# Arduino_Heated_Seats_Controller.net
KiCad netlist of a schematic drawn in EAGLE
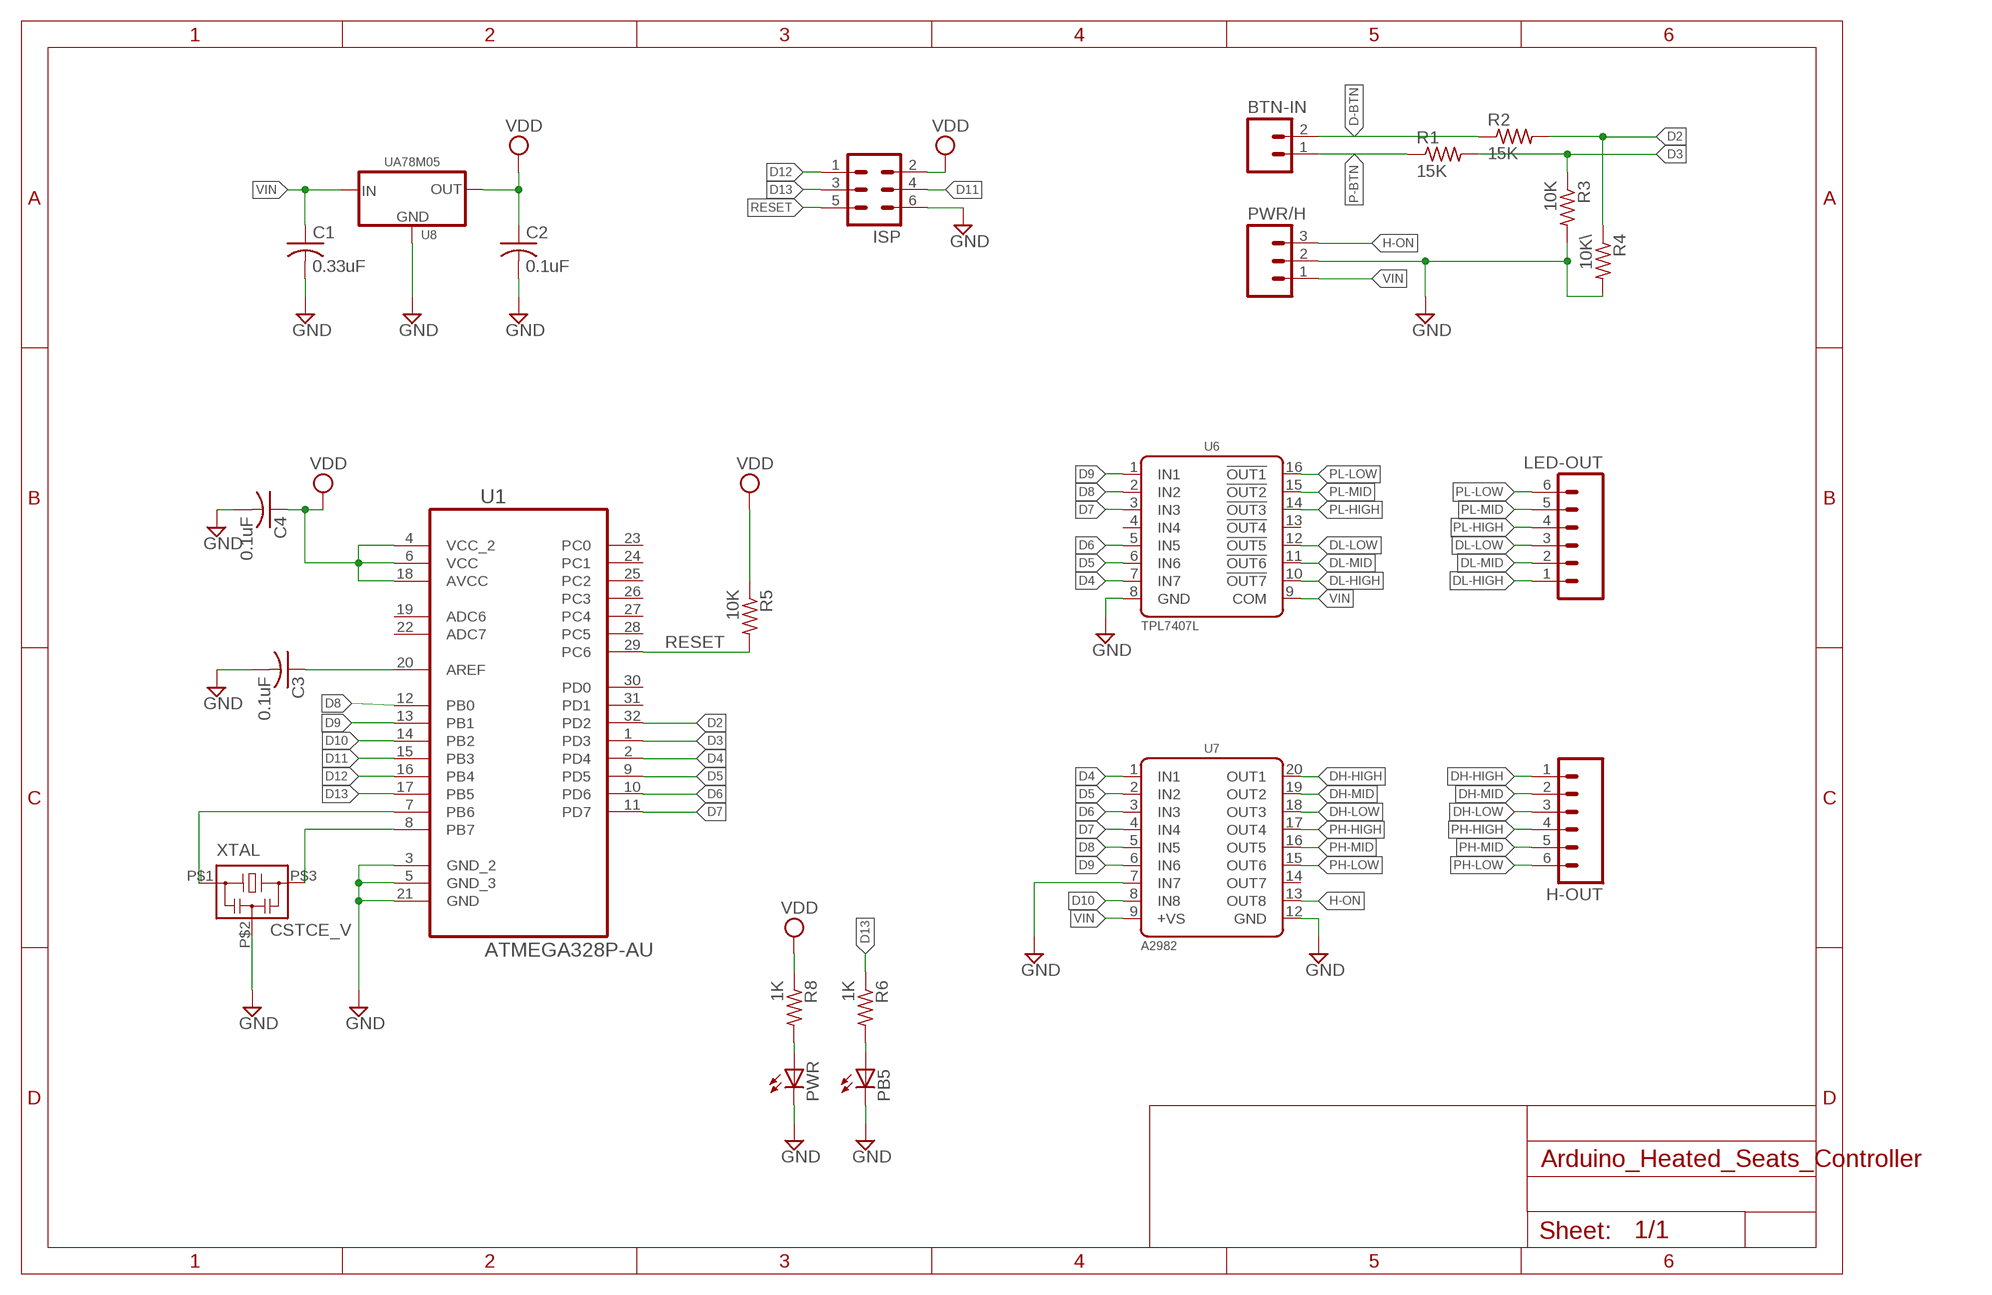
[diagram p0: schematic, sheet 1]

(export (version "E")
  (design (tool "Eeschema 10.0.6"))
  (components
    (comp (ref "BTN-IN")
      (value "M02PTH")
      (footprint "eagle-import:1X02")
      (libsource (lib "eagle-import") (part "M02PTH"))
    )
    (comp (ref "C1")
      (value "0.33uF")
      (footprint "eagle-import:C0603")
      (libsource (lib "eagle-import") (part "C-USC0603"))
    )
    (comp (ref "C2")
      (value "0.1uF")
      (footprint "eagle-import:C0603")
      (libsource (lib "eagle-import") (part "C-USC0603"))
    )
    (comp (ref "C3")
      (value "0.1uF")
      (footprint "eagle-import:C0603")
      (libsource (lib "eagle-import") (part "C-USC0603"))
    )
    (comp (ref "C4")
      (value "0.1uF")
      (footprint "eagle-import:C0603")
      (libsource (lib "eagle-import") (part "C-USC0603"))
    )
    (comp (ref "H-OUT")
      (value "M06SIP")
      (footprint "eagle-import:1X06")
      (libsource (lib "eagle-import") (part "M06SIP"))
    )
    (comp (ref "ISP")
      (value "MA03-2")
      (footprint "eagle-import:MA03-2")
      (libsource (lib "eagle-import") (part "MA03-2"))
    )
    (comp (ref "LED-OUT")
      (value "M06SIP")
      (footprint "eagle-import:1X06")
      (libsource (lib "eagle-import") (part "M06SIP"))
    )
    (comp (ref "PB5")
      (value "LEDCHIP-LED0603")
      (footprint "eagle-import:CHIP-LED0603")
      (libsource (lib "eagle-import") (part "LEDCHIP-LED0603"))
    )
    (comp (ref "PWR")
      (value "LEDCHIP-LED0603")
      (footprint "eagle-import:CHIP-LED0603")
      (libsource (lib "eagle-import") (part "LEDCHIP-LED0603"))
    )
    (comp (ref "PWR/H")
      (value "M03PTH")
      (footprint "eagle-import:1X03")
      (libsource (lib "eagle-import") (part "M03PTH"))
    )
    (comp (ref "R1")
      (value "15K")
      (footprint "eagle-import:R0603")
      (libsource (lib "eagle-import") (part "R-US_R0603"))
    )
    (comp (ref "R2")
      (value "15K")
      (footprint "eagle-import:R0603")
      (libsource (lib "eagle-import") (part "R-US_R0603"))
    )
    (comp (ref "R3")
      (value "10K")
      (footprint "eagle-import:R0603")
      (libsource (lib "eagle-import") (part "R-US_R0603"))
    )
    (comp (ref "R4")
      (value "10K\\")
      (footprint "eagle-import:R0603")
      (libsource (lib "eagle-import") (part "R-US_R0603"))
    )
    (comp (ref "R5")
      (value "10K")
      (footprint "eagle-import:R0603")
      (libsource (lib "eagle-import") (part "R-US_R0603"))
    )
    (comp (ref "R6")
      (value "1K")
      (footprint "eagle-import:R0603")
      (libsource (lib "eagle-import") (part "R-US_R0603"))
    )
    (comp (ref "R8")
      (value "1K")
      (footprint "eagle-import:R0603")
      (libsource (lib "eagle-import") (part "R-US_R0603"))
    )
    (comp (ref "U1")
      (value "ATMEGA328P-AU")
      (footprint "eagle-import:QFP80P900X900X120-32N")
      (libsource (lib "eagle-import") (part "ATMEGA328P-AU"))
    )
    (comp (ref "U6")
      (value "TPL7407L")
      (footprint "eagle-import:SOIC16N")
      (libsource (lib "eagle-import") (part "TPL7407L"))
    )
    (comp (ref "U7")
      (value "A2982")
      (footprint "eagle-import:SOIC20W")
      (libsource (lib "eagle-import") (part "A2982"))
    )
    (comp (ref "U8")
      (value "UA78M05")
      (footprint "eagle-import:SOT223")
      (libsource (lib "eagle-import") (part "UA78M05"))
    )
    (comp (ref "XTAL")
      (value "CSTCE_V")
      (footprint "eagle-import:CSTCE_V")
      (libsource (lib "eagle-import") (part "CSTCE_V"))
    )
  )
  (nets
    (net (code "1") (name "D-BTN") (class "Default")
      (node (ref "BTN-IN") (pin "2") (pinfunction "2_2") (pintype "passive"))
      (node (ref "R2") (pin "1") (pinfunction "1_1") (pintype "passive"))
    )
    (net (code "2") (name "D2") (class "Default")
      (node (ref "R2") (pin "2") (pinfunction "2_2") (pintype "passive"))
      (node (ref "R4") (pin "1") (pinfunction "1_1") (pintype "passive"))
      (node (ref "U1") (pin "32") (pinfunction "PD2_32") (pintype "bidirectional"))
    )
    (net (code "3") (name "D3") (class "Default")
      (node (ref "R1") (pin "2") (pinfunction "2_2") (pintype "passive"))
      (node (ref "R3") (pin "1") (pinfunction "1_1") (pintype "passive"))
      (node (ref "U1") (pin "1") (pinfunction "PD3_1") (pintype "bidirectional"))
    )
    (net (code "4") (name "D4") (class "Default")
      (node (ref "U1") (pin "2") (pinfunction "PD4_2") (pintype "bidirectional"))
      (node (ref "U6") (pin "7") (pinfunction "IN7_7") (pintype "bidirectional"))
      (node (ref "U7") (pin "1") (pinfunction "IN1_1") (pintype "bidirectional"))
    )
    (net (code "5") (name "D5") (class "Default")
      (node (ref "U1") (pin "9") (pinfunction "PD5_9") (pintype "bidirectional"))
      (node (ref "U6") (pin "6") (pinfunction "IN6_6") (pintype "bidirectional"))
      (node (ref "U7") (pin "2") (pinfunction "IN2_2") (pintype "bidirectional"))
    )
    (net (code "6") (name "D6") (class "Default")
      (node (ref "U1") (pin "10") (pinfunction "PD6_10") (pintype "bidirectional"))
      (node (ref "U6") (pin "5") (pinfunction "IN5_5") (pintype "bidirectional"))
      (node (ref "U7") (pin "3") (pinfunction "IN3_3") (pintype "bidirectional"))
    )
    (net (code "7") (name "D7") (class "Default")
      (node (ref "U1") (pin "11") (pinfunction "PD7_11") (pintype "bidirectional"))
      (node (ref "U6") (pin "3") (pinfunction "IN3_3") (pintype "bidirectional"))
      (node (ref "U7") (pin "4") (pinfunction "IN4_4") (pintype "bidirectional"))
    )
    (net (code "8") (name "D8") (class "Default")
      (node (ref "U1") (pin "12") (pinfunction "PB0_12") (pintype "bidirectional"))
      (node (ref "U6") (pin "2") (pinfunction "IN2_2") (pintype "bidirectional"))
      (node (ref "U7") (pin "5") (pinfunction "IN5_5") (pintype "bidirectional"))
    )
    (net (code "9") (name "D9") (class "Default")
      (node (ref "U1") (pin "13") (pinfunction "PB1_13") (pintype "bidirectional"))
      (node (ref "U6") (pin "1") (pinfunction "IN1_1") (pintype "bidirectional"))
      (node (ref "U7") (pin "6") (pinfunction "IN6_6") (pintype "bidirectional"))
    )
    (net (code "10") (name "D10") (class "Default")
      (node (ref "U1") (pin "14") (pinfunction "PB2_14") (pintype "bidirectional"))
      (node (ref "U7") (pin "8") (pinfunction "IN8_8") (pintype "bidirectional"))
    )
    (net (code "11") (name "D11") (class "Default")
      (node (ref "ISP") (pin "4") (pinfunction "4_4") (pintype "passive"))
      (node (ref "U1") (pin "15") (pinfunction "PB3_15") (pintype "bidirectional"))
    )
    (net (code "12") (name "D12") (class "Default")
      (node (ref "ISP") (pin "1") (pinfunction "1_1") (pintype "passive"))
      (node (ref "U1") (pin "16") (pinfunction "PB4_16") (pintype "bidirectional"))
    )
    (net (code "13") (name "D13") (class "Default")
      (node (ref "ISP") (pin "3") (pinfunction "3_3") (pintype "passive"))
      (node (ref "R6") (pin "1") (pinfunction "1_1") (pintype "passive"))
      (node (ref "U1") (pin "17") (pinfunction "PB5_17") (pintype "bidirectional"))
    )
    (net (code "14") (name "DH-HIGH") (class "Default")
      (node (ref "H-OUT") (pin "1") (pinfunction "1_1") (pintype "passive"))
      (node (ref "U7") (pin "20") (pinfunction "OUT1_20") (pintype "bidirectional"))
    )
    (net (code "15") (name "DH-LOW") (class "Default")
      (node (ref "H-OUT") (pin "3") (pinfunction "3_3") (pintype "passive"))
      (node (ref "U7") (pin "18") (pinfunction "OUT3_18") (pintype "bidirectional"))
    )
    (net (code "16") (name "DH-MID") (class "Default")
      (node (ref "H-OUT") (pin "2") (pinfunction "2_2") (pintype "passive"))
      (node (ref "U7") (pin "19") (pinfunction "OUT2_19") (pintype "bidirectional"))
    )
    (net (code "17") (name "DL-HIGH") (class "Default")
      (node (ref "LED-OUT") (pin "1") (pinfunction "1_1") (pintype "passive"))
      (node (ref "U6") (pin "10") (pinfunction "~{OUT7}_10") (pintype "bidirectional"))
    )
    (net (code "18") (name "DL-LOW") (class "Default")
      (node (ref "LED-OUT") (pin "3") (pinfunction "3_3") (pintype "passive"))
      (node (ref "U6") (pin "12") (pinfunction "~{OUT5}_12") (pintype "bidirectional"))
    )
    (net (code "19") (name "DL-MID") (class "Default")
      (node (ref "LED-OUT") (pin "2") (pinfunction "2_2") (pintype "passive"))
      (node (ref "U6") (pin "11") (pinfunction "~{OUT6}_11") (pintype "bidirectional"))
    )
    (net (code "20") (name "GND") (class "Default")
      (node (ref "C1") (pin "2") (pinfunction "2_2") (pintype "passive"))
      (node (ref "C2") (pin "2") (pinfunction "2_2") (pintype "passive"))
      (node (ref "C3") (pin "2") (pinfunction "2_2") (pintype "passive"))
      (node (ref "C4") (pin "2") (pinfunction "2_2") (pintype "passive"))
      (node (ref "ISP") (pin "6") (pinfunction "6_6") (pintype "passive"))
      (node (ref "PB5") (pin "C") (pinfunction "C_C") (pintype "passive"))
      (node (ref "PWR") (pin "C") (pinfunction "C_C") (pintype "passive"))
      (node (ref "PWR/H") (pin "2") (pinfunction "2_2") (pintype "passive"))
      (node (ref "R3") (pin "2") (pinfunction "2_2") (pintype "passive"))
      (node (ref "R4") (pin "2") (pinfunction "2_2") (pintype "passive"))
      (node (ref "U1") (pin "21") (pinfunction "GND_21") (pintype "passive"))
      (node (ref "U1") (pin "3") (pinfunction "GND_2_3") (pintype "passive"))
      (node (ref "U1") (pin "5") (pinfunction "GND_3_5") (pintype "passive"))
      (node (ref "U6") (pin "8") (pinfunction "GND_8") (pintype "bidirectional"))
      (node (ref "U7") (pin "12") (pinfunction "GND_12") (pintype "bidirectional"))
      (node (ref "U7") (pin "7") (pinfunction "IN7_7") (pintype "bidirectional"))
      (node (ref "U8") (pin "2") (pinfunction "GND_2") (pintype "input"))
      (node (ref "XTAL") (pin "P$2") (pinfunction "2_P$2") (pintype "passive"))
    )
    (net (code "21") (name "H-ON") (class "Default")
      (node (ref "PWR/H") (pin "3") (pinfunction "3_3") (pintype "passive"))
      (node (ref "U7") (pin "13") (pinfunction "OUT8_13") (pintype "bidirectional"))
    )
    (net (code "22") (name "Net-(PB5-PadA)") (class "Default")
      (node (ref "PB5") (pin "A") (pinfunction "A_A") (pintype "passive"))
      (node (ref "R6") (pin "2") (pinfunction "2_2") (pintype "passive"))
    )
    (net (code "23") (name "Net-(PWR-PadA)") (class "Default")
      (node (ref "PWR") (pin "A") (pinfunction "A_A") (pintype "passive"))
      (node (ref "R8") (pin "2") (pinfunction "2_2") (pintype "passive"))
    )
    (net (code "24") (name "Net-(U1-AREF)") (class "Default")
      (node (ref "C3") (pin "1") (pinfunction "1_1") (pintype "passive"))
      (node (ref "U1") (pin "20") (pinfunction "AREF_20") (pintype "input"))
    )
    (net (code "25") (name "Net-(U1-PB6)") (class "Default")
      (node (ref "U1") (pin "7") (pinfunction "PB6_7") (pintype "bidirectional"))
      (node (ref "XTAL") (pin "P$1") (pinfunction "1_P$1") (pintype "passive"))
    )
    (net (code "26") (name "Net-(U1-PB7)") (class "Default")
      (node (ref "U1") (pin "8") (pinfunction "PB7_8") (pintype "bidirectional"))
      (node (ref "XTAL") (pin "P$3") (pinfunction "3_P$3") (pintype "passive"))
    )
    (net (code "27") (name "P-BTN") (class "Default")
      (node (ref "BTN-IN") (pin "1") (pinfunction "1_1") (pintype "passive"))
      (node (ref "R1") (pin "1") (pinfunction "1_1") (pintype "passive"))
    )
    (net (code "28") (name "PH-HIGH") (class "Default")
      (node (ref "H-OUT") (pin "4") (pinfunction "4_4") (pintype "passive"))
      (node (ref "U7") (pin "17") (pinfunction "OUT4_17") (pintype "bidirectional"))
    )
    (net (code "29") (name "PH-LOW") (class "Default")
      (node (ref "H-OUT") (pin "6") (pinfunction "6_6") (pintype "passive"))
      (node (ref "U7") (pin "15") (pinfunction "OUT6_15") (pintype "bidirectional"))
    )
    (net (code "30") (name "PH-MID") (class "Default")
      (node (ref "H-OUT") (pin "5") (pinfunction "5_5") (pintype "passive"))
      (node (ref "U7") (pin "16") (pinfunction "OUT5_16") (pintype "bidirectional"))
    )
    (net (code "31") (name "PL-HIGH") (class "Default")
      (node (ref "LED-OUT") (pin "4") (pinfunction "4_4") (pintype "passive"))
      (node (ref "U6") (pin "14") (pinfunction "~{OUT3}_14") (pintype "bidirectional"))
    )
    (net (code "32") (name "PL-LOW") (class "Default")
      (node (ref "LED-OUT") (pin "6") (pinfunction "6_6") (pintype "passive"))
      (node (ref "U6") (pin "16") (pinfunction "~{OUT1}_16") (pintype "bidirectional"))
    )
    (net (code "33") (name "PL-MID") (class "Default")
      (node (ref "LED-OUT") (pin "5") (pinfunction "5_5") (pintype "passive"))
      (node (ref "U6") (pin "15") (pinfunction "~{OUT2}_15") (pintype "bidirectional"))
    )
    (net (code "34") (name "RESET") (class "Default")
      (node (ref "ISP") (pin "5") (pinfunction "5_5") (pintype "passive"))
      (node (ref "R5") (pin "2") (pinfunction "2_2") (pintype "passive"))
      (node (ref "U1") (pin "29") (pinfunction "PC6_29") (pintype "bidirectional"))
    )
    (net (code "35") (name "VDD") (class "Default")
      (node (ref "C2") (pin "1") (pinfunction "1_1") (pintype "passive"))
      (node (ref "C4") (pin "1") (pinfunction "1_1") (pintype "passive"))
      (node (ref "ISP") (pin "2") (pinfunction "2_2") (pintype "passive"))
      (node (ref "R5") (pin "1") (pinfunction "1_1") (pintype "passive"))
      (node (ref "R8") (pin "1") (pinfunction "1_1") (pintype "passive"))
      (node (ref "U1") (pin "18") (pinfunction "AVCC_18") (pintype "power_in"))
      (node (ref "U1") (pin "4") (pinfunction "VCC_2_4") (pintype "power_in"))
      (node (ref "U1") (pin "6") (pinfunction "VCC_6") (pintype "power_in"))
      (node (ref "U8") (pin "3") (pinfunction "OUT_3") (pintype "passive"))
    )
    (net (code "36") (name "VIN") (class "Default")
      (node (ref "C1") (pin "1") (pinfunction "1_1") (pintype "passive"))
      (node (ref "PWR/H") (pin "1") (pinfunction "1_1") (pintype "passive"))
      (node (ref "U6") (pin "9") (pinfunction "COM_9") (pintype "bidirectional"))
      (node (ref "U7") (pin "9") (pinfunction "+VS_9") (pintype "bidirectional"))
      (node (ref "U8") (pin "1") (pinfunction "IN_1") (pintype "input"))
    )
    (net (code "37") (name "unconnected-(U1-ADC6-Pad19)") (class "Default")
      (node (ref "U1") (pin "19") (pinfunction "ADC6_19") (pintype "input"))
    )
    (net (code "38") (name "unconnected-(U1-ADC7-Pad22)") (class "Default")
      (node (ref "U1") (pin "22") (pinfunction "ADC7_22") (pintype "input"))
    )
    (net (code "39") (name "unconnected-(U1-PC0-Pad23)") (class "Default")
      (node (ref "U1") (pin "23") (pinfunction "PC0_23") (pintype "bidirectional"))
    )
    (net (code "40") (name "unconnected-(U1-PC1-Pad24)") (class "Default")
      (node (ref "U1") (pin "24") (pinfunction "PC1_24") (pintype "bidirectional"))
    )
    (net (code "41") (name "unconnected-(U1-PC2-Pad25)") (class "Default")
      (node (ref "U1") (pin "25") (pinfunction "PC2_25") (pintype "bidirectional"))
    )
    (net (code "42") (name "unconnected-(U1-PC3-Pad26)") (class "Default")
      (node (ref "U1") (pin "26") (pinfunction "PC3_26") (pintype "bidirectional"))
    )
    (net (code "43") (name "unconnected-(U1-PC4-Pad27)") (class "Default")
      (node (ref "U1") (pin "27") (pinfunction "PC4_27") (pintype "bidirectional"))
    )
    (net (code "44") (name "unconnected-(U1-PC5-Pad28)") (class "Default")
      (node (ref "U1") (pin "28") (pinfunction "PC5_28") (pintype "bidirectional"))
    )
    (net (code "45") (name "unconnected-(U1-PD0-Pad30)") (class "Default")
      (node (ref "U1") (pin "30") (pinfunction "PD0_30") (pintype "bidirectional"))
    )
    (net (code "46") (name "unconnected-(U1-PD1-Pad31)") (class "Default")
      (node (ref "U1") (pin "31") (pinfunction "PD1_31") (pintype "bidirectional"))
    )
    (net (code "47") (name "unconnected-(U6-IN4-Pad4)") (class "Default")
      (node (ref "U6") (pin "4") (pinfunction "IN4_4") (pintype "bidirectional"))
    )
    (net (code "48") (name "unconnected-(U6-~{OUT4}-Pad13)") (class "Default")
      (node (ref "U6") (pin "13") (pinfunction "~{OUT4}_13") (pintype "bidirectional"))
    )
    (net (code "49") (name "unconnected-(U7-OUT7-Pad14)") (class "Default")
      (node (ref "U7") (pin "14") (pinfunction "OUT7_14") (pintype "bidirectional"))
    )
  )
)
